# Regulador_3v3.net
KiCad netlist of a schematic drawn in Altium Designer
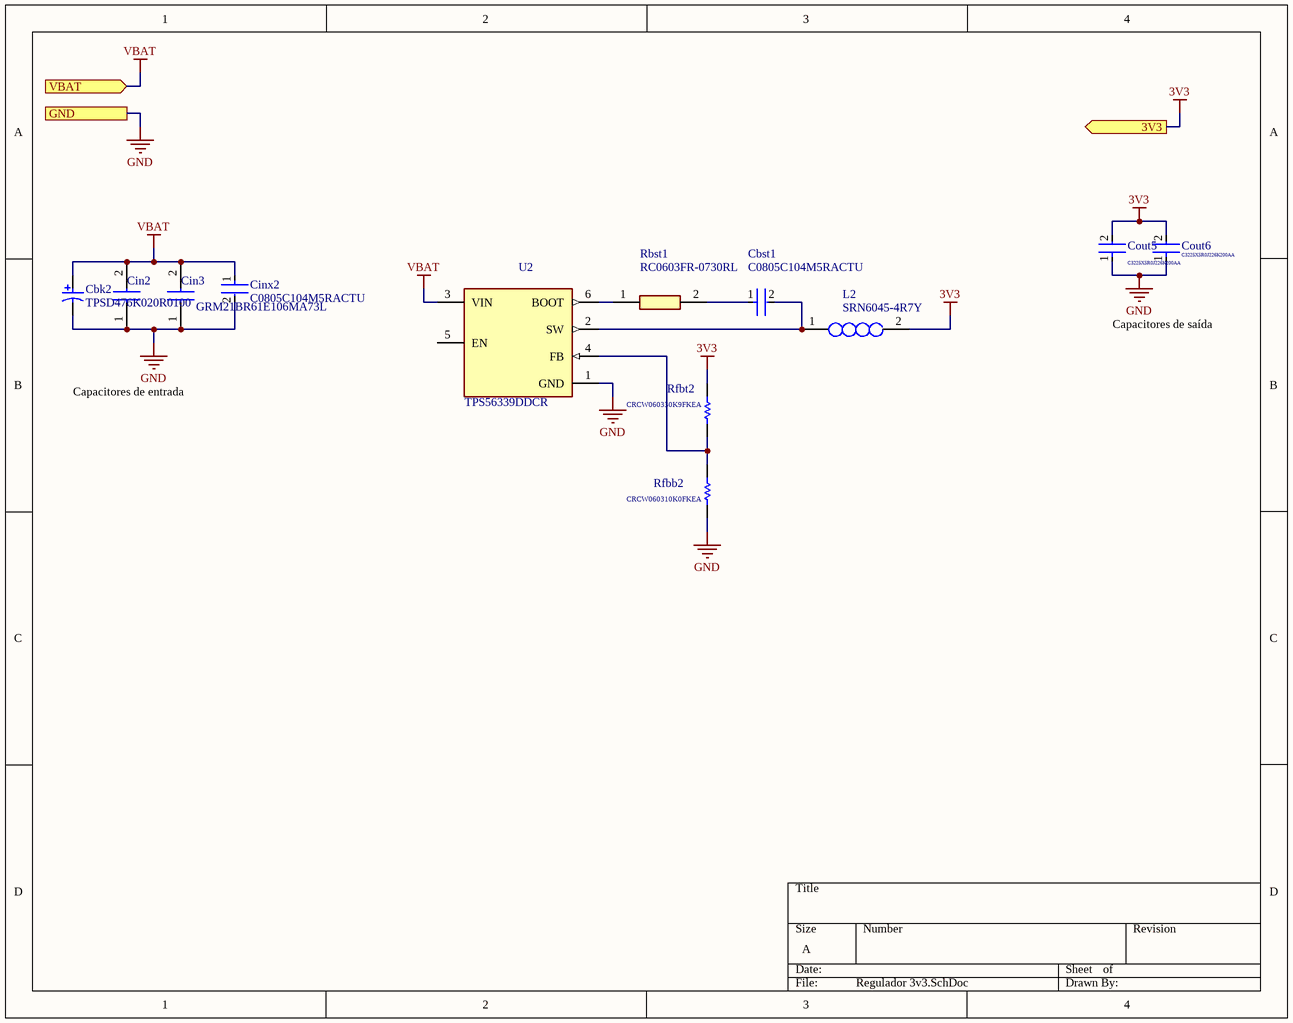
[diagram p0: Regulador 3v3.SchDoc]

(export (version "E")
  (design (tool "Eeschema 10.0.6"))
  (components
    (comp (ref "Cbk2")
      (value "TPSD476K020R0100")
      (footprint "TPSD476K020R0100")
      (description "CAP TANT 47UF 20V 10% 2917")
      (fields (field (name "MANUFACTURER") "Kyocera AVX") (field (name "TOLERANCE") "10%"))
      (libsource (lib "Schlib1") (part "TPSD476K020R0100"))
    )
    (comp (ref "Cbst1")
      (value "C0805C104M5RACTU")
      (footprint "FP-C0805C-DN-MFG")
      (description "CAP CER 0.1UF 50V X7R 0805")
      (fields
        (field (name "TOLERANCE") "0.2")
        (field (name "OCTOPART") "https://octopart.com/c0805c104m5ractu-kemet-129379")
      )
      (libsource (lib "Altium Content Vault") (part "b4654b650e69147ec39a6b967a45e02"))
    )
    (comp (ref "Cin2")
      (value "GRM21BR61E106MA73L")
      (footprint "GRM21BR61E106MA73L:CAPC2012X145N")
      (description "Capacitor")
      (fields (field (name "MOUSER2 PART NUMBER") "81-GRM21BR61E106MA3L"))
      (libsource (lib "*") (part "GRM21BR61E106MA73L"))
    )
    (comp (ref "Cin3")
      (value "GRM21BR61E106MA73L")
      (footprint "GRM21BR61E106MA73L:CAPC2012X145N")
      (description "Capacitor")
      (fields (field (name "MOUSER2 PART NUMBER") "81-GRM21BR61E106MA3L"))
      (libsource (lib "*") (part "GRM21BR61E106MA73L"))
    )
    (comp (ref "Cinx2")
      (value "C0805C104M5RACTU")
      (footprint "FP-C0805C-DN-MFG")
      (description "CAP CER 0.1UF 50V X7R 0805")
      (fields
        (field (name "TOLERANCE") "0.2")
        (field (name "OCTOPART") "https://octopart.com/c0805c104m5ractu-kemet-129379")
      )
      (libsource (lib "Altium Content Vault") (part "b4654b650e69147ec39a6b967a45e02"))
    )
    (comp (ref "Cout5")
      (value "C3225X5R0J226K200AA")
      (footprint "FP-C3225-200-0_4-IPC_C")
      (description "Multilayer Ceramic Capacitors 22uF ±10% 6.3V X5R SMD 1210")
      (fields (field (name "VOLTAGE") "6.3V") (field (name "TOLERANCE") "10%"))
      (libsource (lib "Altium Content Vault") (part "b4654b650e69147ec39a6b967a45e02"))
    )
    (comp (ref "Cout6")
      (value "C3225X5R0J226K200AA")
      (footprint "FP-C3225-200-0_4-IPC_C")
      (description "Multilayer Ceramic Capacitors 22uF ±10% 6.3V X5R SMD 1210")
      (fields (field (name "VOLTAGE") "6.3V") (field (name "TOLERANCE") "10%"))
      (libsource (lib "Altium Content Vault") (part "b4654b650e69147ec39a6b967a45e02"))
    )
    (comp (ref "L2")
      (value "SRN6045-4R7Y")
      (footprint "SRN6045-4R7Y-pcb-part-libraries:SRN6045_1")
      (description "Inductor")
      (libsource (lib "*") (part "SRN6045-4R7Y"))
    )
    (comp (ref "Rbst1")
      (value "RC0603FR-0730RL")
      (footprint "RC0603FR-0730RL:RESC1608X55N")
      (description "Resistor")
      (libsource (lib "*") (part "RC0603FR-0730RL"))
    )
    (comp (ref "Rfbb2")
      (value "CRCW060310K0FKEA")
      (footprint "RESC1609X50X30NL8T20")
      (description "Chip Resistor, 10 KOhm, +/- 1%, 100 mW, -55 to 155 degC, 0603 (1608 Metric), RoHS, Tape and Reel")
      (fields (field (name "MANUFACTURER") "Vishay Semiconductor"))
      (libsource (lib "Altium Content Vault") (part "RES-2"))
    )
    (comp (ref "Rfbt2")
      (value "CRCW060330K9FKEA")
      (footprint "RESC1609X50X30LL10T20")
      (fields (field (name "MANUFACTURER") "Vishay Dale"))
      (libsource (lib "Altium Content Vault") (part "RES"))
    )
    (comp (ref "U2")
      (value "TPS56339DDCR")
      (footprint "FP-DDC0006A-MFG")
      (description "PWR MGMT SPECIALIZED REGULATOR")
      (fields
        (field (name "MANUFACTURER") "Texas Instruments")
        (field (name "OCTOPART") "https://octopart.com/tps56339ddcr-texas+instruments-101466410")
      )
      (libsource (lib "Altium Content Vault") (part "2ef13c8a92b2ccd2de8c1984d71b5d5"))
    )
  )
  (nets
    (net (code "1") (name "3V3") (class "Default")
      (node (ref "Cout5") (pin "2") (pinfunction "2_2") (pintype "passive"))
      (node (ref "Cout6") (pin "2") (pinfunction "2_2") (pintype "passive"))
      (node (ref "L2") (pin "2") (pinfunction "2_2") (pintype "passive"))
      (node (ref "Rfbt2") (pin "2") (pinfunction "2_2") (pintype "passive"))
    )
    (net (code "2") (name "GND") (class "Default")
      (node (ref "Cbk2") (pin "2") (pinfunction "2_2") (pintype "passive"))
      (node (ref "Cin2") (pin "1") (pinfunction "1_1") (pintype "passive"))
      (node (ref "Cin3") (pin "1") (pinfunction "1_1") (pintype "passive"))
      (node (ref "Cinx2") (pin "2") (pinfunction "2_2") (pintype "passive"))
      (node (ref "Cout5") (pin "1") (pinfunction "1_1") (pintype "passive"))
      (node (ref "Cout6") (pin "1") (pinfunction "1_1") (pintype "passive"))
      (node (ref "Rfbb2") (pin "2") (pinfunction "2_2") (pintype "passive"))
      (node (ref "U2") (pin "1") (pinfunction "GND_1") (pintype "power_in"))
    )
    (net (code "3") (name "Net-(Cbst1-Pad1)") (class "Default")
      (node (ref "Cbst1") (pin "1") (pinfunction "1_1") (pintype "passive"))
      (node (ref "Rbst1") (pin "2") (pinfunction "2_2") (pintype "passive"))
    )
    (net (code "4") (name "Net-(U2-BOOT)") (class "Default")
      (node (ref "Rbst1") (pin "1") (pinfunction "1_1") (pintype "passive"))
      (node (ref "U2") (pin "6") (pinfunction "BOOT_6") (pintype "output"))
    )
    (net (code "5") (name "Net-(U2-FB)") (class "Default")
      (node (ref "Rfbb2") (pin "1") (pinfunction "1_1") (pintype "passive"))
      (node (ref "Rfbt2") (pin "1") (pinfunction "1_1") (pintype "passive"))
      (node (ref "U2") (pin "4") (pinfunction "FB_4") (pintype "input"))
    )
    (net (code "6") (name "Net-(U2-SW)") (class "Default")
      (node (ref "Cbst1") (pin "2") (pinfunction "2_2") (pintype "passive"))
      (node (ref "L2") (pin "1") (pinfunction "1_1") (pintype "passive"))
      (node (ref "U2") (pin "2") (pinfunction "SW_2") (pintype "output"))
    )
    (net (code "7") (name "VBAT") (class "Default")
      (node (ref "Cbk2") (pin "1") (pinfunction "1_1") (pintype "passive"))
      (node (ref "Cin2") (pin "2") (pinfunction "2_2") (pintype "passive"))
      (node (ref "Cin3") (pin "2") (pinfunction "2_2") (pintype "passive"))
      (node (ref "Cinx2") (pin "1") (pinfunction "1_1") (pintype "passive"))
      (node (ref "U2") (pin "3") (pinfunction "VIN_3") (pintype "passive"))
    )
    (net (code "8") (name "unconnected-(U2-EN-Pad5)") (class "Default")
      (node (ref "U2") (pin "5") (pinfunction "EN_5") (pintype "passive"))
    )
  )
)
